# DDR3.net
KiCad netlist of a schematic drawn in Altium Designer
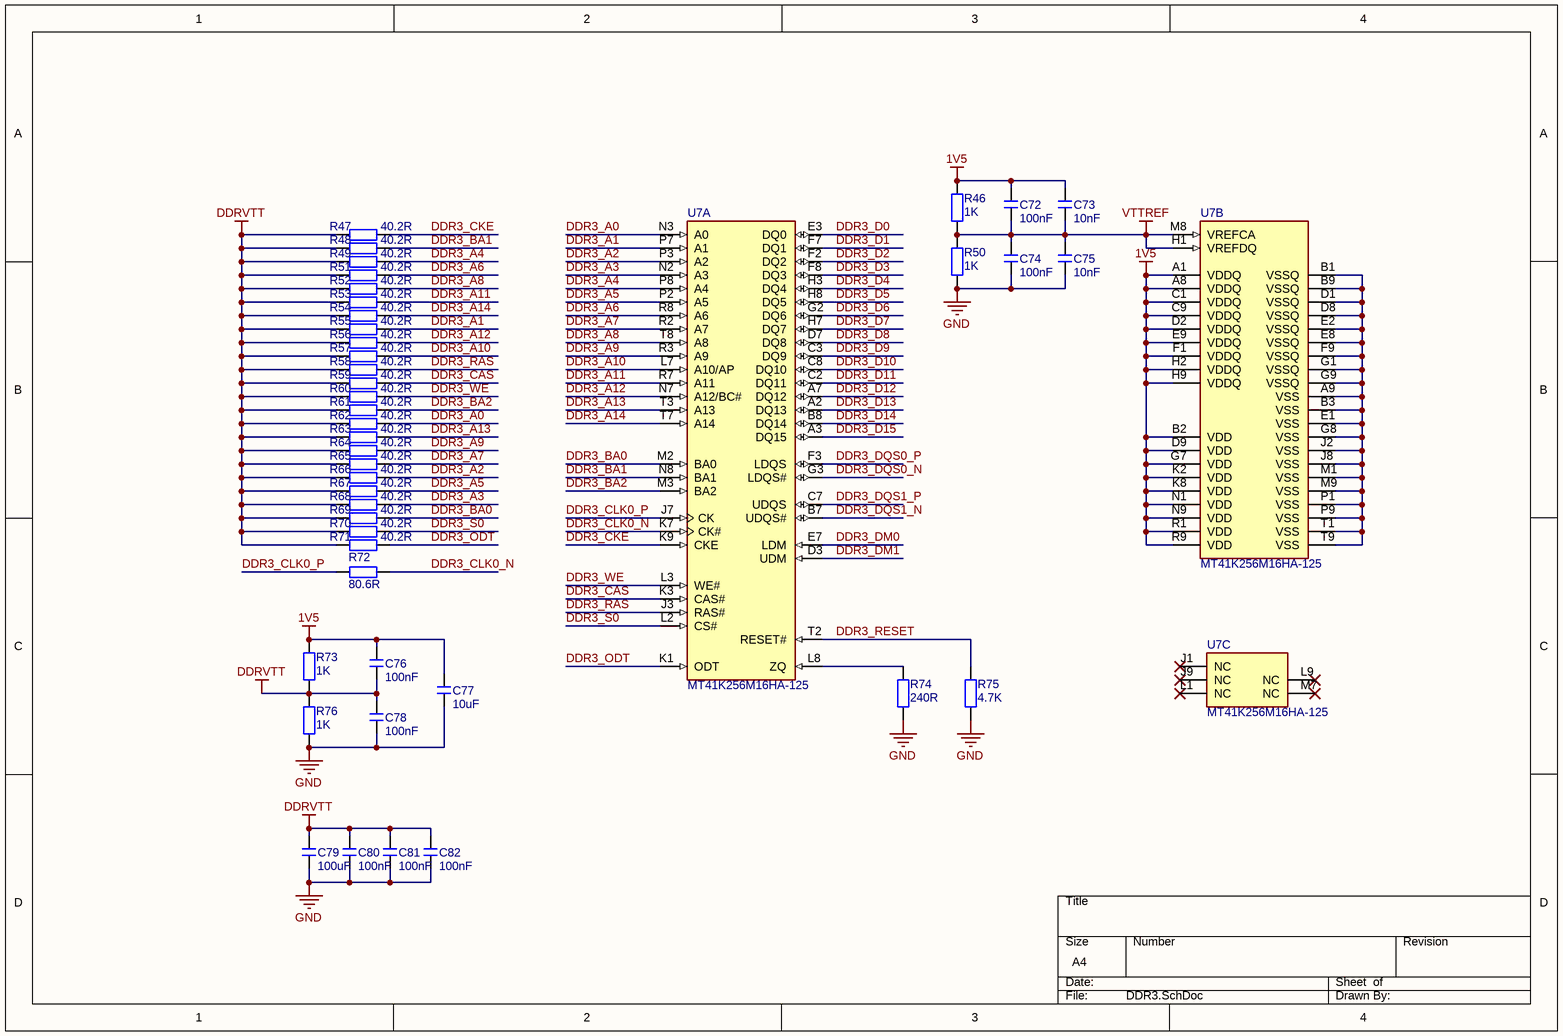
[diagram p0: DDR3.SchDoc]

(export (version "E")
  (design (tool "Eeschema 10.0.6"))
  (components
    (comp (ref "C72")
      (value "100nF")
      (footprint "C 0402_L")
      (description "无极性贴片电容")
      (fields (field (name "版权归属") "源创客"))
      (libsource (lib "3.1   - 电阻-电容-电感") (part "C"))
    )
    (comp (ref "C73")
      (value "10nF")
      (footprint "C 0402_L")
      (description "无极性贴片电容")
      (fields (field (name "版权归属") "源创客"))
      (libsource (lib "3.1   - 电阻-电容-电感") (part "C"))
    )
    (comp (ref "C74")
      (value "100nF")
      (footprint "C 0402_L")
      (description "无极性贴片电容")
      (fields (field (name "版权归属") "源创客"))
      (libsource (lib "3.1   - 电阻-电容-电感") (part "C"))
    )
    (comp (ref "C75")
      (value "10nF")
      (footprint "C 0402_L")
      (description "无极性贴片电容")
      (fields (field (name "版权归属") "源创客"))
      (libsource (lib "3.1   - 电阻-电容-电感") (part "C"))
    )
    (comp (ref "C76")
      (value "100nF")
      (footprint "C 0402_L")
      (description "无极性贴片电容")
      (fields (field (name "版权归属") "源创客"))
      (libsource (lib "3.1   - 电阻-电容-电感") (part "C"))
    )
    (comp (ref "C77")
      (value "10uF")
      (footprint "C 0603_L")
      (description "无极性贴片电容")
      (fields (field (name "版权归属") "源创客"))
      (libsource (lib "3.1   - 电阻-电容-电感") (part "C"))
    )
    (comp (ref "C78")
      (value "100nF")
      (footprint "C 0402_L")
      (description "无极性贴片电容")
      (fields (field (name "版权归属") "源创客"))
      (libsource (lib "3.1   - 电阻-电容-电感") (part "C"))
    )
    (comp (ref "C79")
      (value "100uF")
      (footprint "C 0805_L")
      (description "无极性贴片电容")
      (fields (field (name "版权归属") "源创客"))
      (libsource (lib "3.1   - 电阻-电容-电感") (part "C"))
    )
    (comp (ref "C80")
      (value "100nF")
      (footprint "C 0402_L")
      (description "无极性贴片电容")
      (fields (field (name "版权归属") "源创客"))
      (libsource (lib "3.1   - 电阻-电容-电感") (part "C"))
    )
    (comp (ref "C81")
      (value "100nF")
      (footprint "C 0402_L")
      (description "无极性贴片电容")
      (fields (field (name "版权归属") "源创客"))
      (libsource (lib "3.1   - 电阻-电容-电感") (part "C"))
    )
    (comp (ref "C82")
      (value "100nF")
      (footprint "C 0402_L")
      (description "无极性贴片电容")
      (fields (field (name "版权归属") "源创客"))
      (libsource (lib "3.1   - 电阻-电容-电感") (part "C"))
    )
    (comp (ref "R46")
      (value "1K")
      (footprint "R 0402_L")
      (description "贴片电阻")
      (fields (field (name "版权归属") "源创客"))
      (libsource (lib "3.1   - 电阻-电容-电感") (part "R"))
    )
    (comp (ref "R47")
      (value "40.2R")
      (footprint "R 0805_L")
      (description "贴片电阻")
      (fields (field (name "版权归属") "源创客"))
      (libsource (lib "3.1   - 电阻-电容-电感") (part "R"))
    )
    (comp (ref "R48")
      (value "40.2R")
      (footprint "R 0805_L")
      (description "贴片电阻")
      (fields (field (name "版权归属") "源创客"))
      (libsource (lib "3.1   - 电阻-电容-电感") (part "R"))
    )
    (comp (ref "R49")
      (value "40.2R")
      (footprint "R 0805_L")
      (description "贴片电阻")
      (fields (field (name "版权归属") "源创客"))
      (libsource (lib "3.1   - 电阻-电容-电感") (part "R"))
    )
    (comp (ref "R50")
      (value "1K")
      (footprint "R 0402_L")
      (description "贴片电阻")
      (fields (field (name "版权归属") "源创客"))
      (libsource (lib "3.1   - 电阻-电容-电感") (part "R"))
    )
    (comp (ref "R51")
      (value "40.2R")
      (footprint "R 0805_L")
      (description "贴片电阻")
      (fields (field (name "版权归属") "源创客"))
      (libsource (lib "3.1   - 电阻-电容-电感") (part "R"))
    )
    (comp (ref "R52")
      (value "40.2R")
      (footprint "R 0805_L")
      (description "贴片电阻")
      (fields (field (name "版权归属") "源创客"))
      (libsource (lib "3.1   - 电阻-电容-电感") (part "R"))
    )
    (comp (ref "R53")
      (value "40.2R")
      (footprint "R 0805_L")
      (description "贴片电阻")
      (fields (field (name "版权归属") "源创客"))
      (libsource (lib "3.1   - 电阻-电容-电感") (part "R"))
    )
    (comp (ref "R54")
      (value "40.2R")
      (footprint "R 0805_L")
      (description "贴片电阻")
      (fields (field (name "版权归属") "源创客"))
      (libsource (lib "3.1   - 电阻-电容-电感") (part "R"))
    )
    (comp (ref "R55")
      (value "40.2R")
      (footprint "R 0805_L")
      (description "贴片电阻")
      (fields (field (name "版权归属") "源创客"))
      (libsource (lib "3.1   - 电阻-电容-电感") (part "R"))
    )
    (comp (ref "R56")
      (value "40.2R")
      (footprint "R 0805_L")
      (description "贴片电阻")
      (fields (field (name "版权归属") "源创客"))
      (libsource (lib "3.1   - 电阻-电容-电感") (part "R"))
    )
    (comp (ref "R57")
      (value "40.2R")
      (footprint "R 0805_L")
      (description "贴片电阻")
      (fields (field (name "版权归属") "源创客"))
      (libsource (lib "3.1   - 电阻-电容-电感") (part "R"))
    )
    (comp (ref "R58")
      (value "40.2R")
      (footprint "R 0805_L")
      (description "贴片电阻")
      (fields (field (name "版权归属") "源创客"))
      (libsource (lib "3.1   - 电阻-电容-电感") (part "R"))
    )
    (comp (ref "R59")
      (value "40.2R")
      (footprint "R 0805_L")
      (description "贴片电阻")
      (fields (field (name "版权归属") "源创客"))
      (libsource (lib "3.1   - 电阻-电容-电感") (part "R"))
    )
    (comp (ref "R60")
      (value "40.2R")
      (footprint "R 0805_L")
      (description "贴片电阻")
      (fields (field (name "版权归属") "源创客"))
      (libsource (lib "3.1   - 电阻-电容-电感") (part "R"))
    )
    (comp (ref "R61")
      (value "40.2R")
      (footprint "R 0805_L")
      (description "贴片电阻")
      (fields (field (name "版权归属") "源创客"))
      (libsource (lib "3.1   - 电阻-电容-电感") (part "R"))
    )
    (comp (ref "R62")
      (value "40.2R")
      (footprint "R 0805_L")
      (description "贴片电阻")
      (fields (field (name "版权归属") "源创客"))
      (libsource (lib "3.1   - 电阻-电容-电感") (part "R"))
    )
    (comp (ref "R63")
      (value "40.2R")
      (footprint "R 0805_L")
      (description "贴片电阻")
      (fields (field (name "版权归属") "源创客"))
      (libsource (lib "3.1   - 电阻-电容-电感") (part "R"))
    )
    (comp (ref "R64")
      (value "40.2R")
      (footprint "R 0805_L")
      (description "贴片电阻")
      (fields (field (name "版权归属") "源创客"))
      (libsource (lib "3.1   - 电阻-电容-电感") (part "R"))
    )
    (comp (ref "R65")
      (value "40.2R")
      (footprint "R 0805_L")
      (description "贴片电阻")
      (fields (field (name "版权归属") "源创客"))
      (libsource (lib "3.1   - 电阻-电容-电感") (part "R"))
    )
    (comp (ref "R66")
      (value "40.2R")
      (footprint "R 0805_L")
      (description "贴片电阻")
      (fields (field (name "版权归属") "源创客"))
      (libsource (lib "3.1   - 电阻-电容-电感") (part "R"))
    )
    (comp (ref "R67")
      (value "40.2R")
      (footprint "R 0805_L")
      (description "贴片电阻")
      (fields (field (name "版权归属") "源创客"))
      (libsource (lib "3.1   - 电阻-电容-电感") (part "R"))
    )
    (comp (ref "R68")
      (value "40.2R")
      (footprint "R 0805_L")
      (description "贴片电阻")
      (fields (field (name "版权归属") "源创客"))
      (libsource (lib "3.1   - 电阻-电容-电感") (part "R"))
    )
    (comp (ref "R69")
      (value "40.2R")
      (footprint "R 0805_L")
      (description "贴片电阻")
      (fields (field (name "版权归属") "源创客"))
      (libsource (lib "3.1   - 电阻-电容-电感") (part "R"))
    )
    (comp (ref "R70")
      (value "40.2R")
      (footprint "R 0805_L")
      (description "贴片电阻")
      (fields (field (name "版权归属") "源创客"))
      (libsource (lib "3.1   - 电阻-电容-电感") (part "R"))
    )
    (comp (ref "R71")
      (value "40.2R")
      (footprint "R 0805_L")
      (description "贴片电阻")
      (fields (field (name "版权归属") "源创客"))
      (libsource (lib "3.1   - 电阻-电容-电感") (part "R"))
    )
    (comp (ref "R72")
      (value "80.6R")
      (footprint "R 0805_L")
      (description "贴片电阻")
      (fields (field (name "版权归属") "源创客"))
      (libsource (lib "3.1   - 电阻-电容-电感") (part "R"))
    )
    (comp (ref "R73")
      (value "1K")
      (footprint "R 0402_L")
      (description "贴片电阻")
      (fields (field (name "版权归属") "源创客"))
      (libsource (lib "3.1   - 电阻-电容-电感") (part "R"))
    )
    (comp (ref "R74")
      (value "240R")
      (footprint "R 0805_L")
      (description "贴片电阻")
      (fields (field (name "版权归属") "源创客"))
      (libsource (lib "3.1   - 电阻-电容-电感") (part "R"))
    )
    (comp (ref "R75")
      (value "4.7K")
      (footprint "R 0402_L")
      (description "贴片电阻")
      (fields (field (name "版权归属") "源创客"))
      (libsource (lib "3.1   - 电阻-电容-电感") (part "R"))
    )
    (comp (ref "R76")
      (value "1K")
      (footprint "R 0402_L")
      (description "贴片电阻")
      (fields (field (name "版权归属") "源创客"))
      (libsource (lib "3.1   - 电阻-电容-电感") (part "R"))
    )
    (comp (ref "U7")
      (value "MT41K256M16HA-125")
      (footprint "BGA96C80P9X16_800X1300X120")
      (description "DDR3-16位数据-14位地址")
      (libsource (lib "16.1 - DDR-LPDDR") (part "MT41K256M16HA-125"))
    )
  )
  (nets
    (net (code "1") (name "/DDR3_A0") (class "Default")
      (node (ref "R62") (pin "1") (pinfunction "1_1") (pintype "passive"))
      (node (ref "U7") (pin "N3") (pinfunction "A0_N3") (pintype "input"))
    )
    (net (code "2") (name "/DDR3_A1") (class "Default")
      (node (ref "R55") (pin "1") (pinfunction "1_1") (pintype "passive"))
      (node (ref "U7") (pin "P7") (pinfunction "A1_P7") (pintype "input"))
    )
    (net (code "3") (name "/DDR3_A2") (class "Default")
      (node (ref "R66") (pin "1") (pinfunction "1_1") (pintype "passive"))
      (node (ref "U7") (pin "P3") (pinfunction "A2_P3") (pintype "input"))
    )
    (net (code "4") (name "/DDR3_A3") (class "Default")
      (node (ref "R68") (pin "1") (pinfunction "1_1") (pintype "passive"))
      (node (ref "U7") (pin "N2") (pinfunction "A3_N2") (pintype "input"))
    )
    (net (code "5") (name "/DDR3_A4") (class "Default")
      (node (ref "R49") (pin "1") (pinfunction "1_1") (pintype "passive"))
      (node (ref "U7") (pin "P8") (pinfunction "A4_P8") (pintype "input"))
    )
    (net (code "6") (name "/DDR3_A5") (class "Default")
      (node (ref "R67") (pin "1") (pinfunction "1_1") (pintype "passive"))
      (node (ref "U7") (pin "P2") (pinfunction "A5_P2") (pintype "input"))
    )
    (net (code "7") (name "/DDR3_A6") (class "Default")
      (node (ref "R51") (pin "1") (pinfunction "1_1") (pintype "passive"))
      (node (ref "U7") (pin "R8") (pinfunction "A6_R8") (pintype "input"))
    )
    (net (code "8") (name "/DDR3_A7") (class "Default")
      (node (ref "R65") (pin "1") (pinfunction "1_1") (pintype "passive"))
      (node (ref "U7") (pin "R2") (pinfunction "A7_R2") (pintype "input"))
    )
    (net (code "9") (name "/DDR3_A8") (class "Default")
      (node (ref "R52") (pin "1") (pinfunction "1_1") (pintype "passive"))
      (node (ref "U7") (pin "T8") (pinfunction "A8_T8") (pintype "input"))
    )
    (net (code "10") (name "/DDR3_A9") (class "Default")
      (node (ref "R64") (pin "1") (pinfunction "1_1") (pintype "passive"))
      (node (ref "U7") (pin "R3") (pinfunction "A9_R3") (pintype "input"))
    )
    (net (code "11") (name "/DDR3_A10") (class "Default")
      (node (ref "R57") (pin "1") (pinfunction "1_1") (pintype "passive"))
      (node (ref "U7") (pin "L7") (pinfunction "A10/AP_L7") (pintype "input"))
    )
    (net (code "12") (name "/DDR3_A11") (class "Default")
      (node (ref "R53") (pin "1") (pinfunction "1_1") (pintype "passive"))
      (node (ref "U7") (pin "R7") (pinfunction "A11_R7") (pintype "input"))
    )
    (net (code "13") (name "/DDR3_A12") (class "Default")
      (node (ref "R56") (pin "1") (pinfunction "1_1") (pintype "passive"))
      (node (ref "U7") (pin "N7") (pinfunction "A12/BC#_N7") (pintype "input"))
    )
    (net (code "14") (name "/DDR3_A13") (class "Default")
      (node (ref "R63") (pin "1") (pinfunction "1_1") (pintype "passive"))
      (node (ref "U7") (pin "T3") (pinfunction "A13_T3") (pintype "input"))
    )
    (net (code "15") (name "/DDR3_A14") (class "Default")
      (node (ref "R54") (pin "1") (pinfunction "1_1") (pintype "passive"))
      (node (ref "U7") (pin "T7") (pinfunction "A14_T7") (pintype "input"))
    )
    (net (code "16") (name "/DDR3_BA0") (class "Default")
      (node (ref "R69") (pin "1") (pinfunction "1_1") (pintype "passive"))
      (node (ref "U7") (pin "M2") (pinfunction "BA0_M2") (pintype "input"))
    )
    (net (code "17") (name "/DDR3_BA1") (class "Default")
      (node (ref "R48") (pin "1") (pinfunction "1_1") (pintype "passive"))
      (node (ref "U7") (pin "N8") (pinfunction "BA1_N8") (pintype "input"))
    )
    (net (code "18") (name "/DDR3_BA2") (class "Default")
      (node (ref "R61") (pin "1") (pinfunction "1_1") (pintype "passive"))
      (node (ref "U7") (pin "M3") (pinfunction "BA2_M3") (pintype "input"))
    )
    (net (code "19") (name "/DDR3_CAS") (class "Default")
      (node (ref "R59") (pin "1") (pinfunction "1_1") (pintype "passive"))
      (node (ref "U7") (pin "K3") (pinfunction "CAS#_K3") (pintype "input"))
    )
    (net (code "20") (name "/DDR3_CKE") (class "Default")
      (node (ref "R47") (pin "1") (pinfunction "1_1") (pintype "passive"))
      (node (ref "U7") (pin "K9") (pinfunction "CKE_K9") (pintype "input"))
    )
    (net (code "21") (name "/DDR3_CLK0_N") (class "Default")
      (node (ref "R72") (pin "2") (pinfunction "2_2") (pintype "passive"))
      (node (ref "U7") (pin "K7") (pinfunction "CK#_K7") (pintype "input"))
    )
    (net (code "22") (name "/DDR3_CLK0_P") (class "Default")
      (node (ref "R72") (pin "1") (pinfunction "1_1") (pintype "passive"))
      (node (ref "U7") (pin "J7") (pinfunction "CK_J7") (pintype "input"))
    )
    (net (code "23") (name "/DDR3_D0") (class "Default")
      (node (ref "U7") (pin "E3") (pinfunction "DQ0_E3") (pintype "bidirectional"))
    )
    (net (code "24") (name "/DDR3_D1") (class "Default")
      (node (ref "U7") (pin "F7") (pinfunction "DQ1_F7") (pintype "bidirectional"))
    )
    (net (code "25") (name "/DDR3_D2") (class "Default")
      (node (ref "U7") (pin "F2") (pinfunction "DQ2_F2") (pintype "bidirectional"))
    )
    (net (code "26") (name "/DDR3_D3") (class "Default")
      (node (ref "U7") (pin "F8") (pinfunction "DQ3_F8") (pintype "bidirectional"))
    )
    (net (code "27") (name "/DDR3_D4") (class "Default")
      (node (ref "U7") (pin "H3") (pinfunction "DQ4_H3") (pintype "bidirectional"))
    )
    (net (code "28") (name "/DDR3_D5") (class "Default")
      (node (ref "U7") (pin "H8") (pinfunction "DQ5_H8") (pintype "bidirectional"))
    )
    (net (code "29") (name "/DDR3_D6") (class "Default")
      (node (ref "U7") (pin "G2") (pinfunction "DQ6_G2") (pintype "bidirectional"))
    )
    (net (code "30") (name "/DDR3_D7") (class "Default")
      (node (ref "U7") (pin "H7") (pinfunction "DQ7_H7") (pintype "bidirectional"))
    )
    (net (code "31") (name "/DDR3_D8") (class "Default")
      (node (ref "U7") (pin "D7") (pinfunction "DQ8_D7") (pintype "bidirectional"))
    )
    (net (code "32") (name "/DDR3_D9") (class "Default")
      (node (ref "U7") (pin "C3") (pinfunction "DQ9_C3") (pintype "bidirectional"))
    )
    (net (code "33") (name "/DDR3_D10") (class "Default")
      (node (ref "U7") (pin "C8") (pinfunction "DQ10_C8") (pintype "bidirectional"))
    )
    (net (code "34") (name "/DDR3_D11") (class "Default")
      (node (ref "U7") (pin "C2") (pinfunction "DQ11_C2") (pintype "bidirectional"))
    )
    (net (code "35") (name "/DDR3_D12") (class "Default")
      (node (ref "U7") (pin "A7") (pinfunction "DQ12_A7") (pintype "bidirectional"))
    )
    (net (code "36") (name "/DDR3_D13") (class "Default")
      (node (ref "U7") (pin "A2") (pinfunction "DQ13_A2") (pintype "bidirectional"))
    )
    (net (code "37") (name "/DDR3_D14") (class "Default")
      (node (ref "U7") (pin "B8") (pinfunction "DQ14_B8") (pintype "bidirectional"))
    )
    (net (code "38") (name "/DDR3_D15") (class "Default")
      (node (ref "U7") (pin "A3") (pinfunction "DQ15_A3") (pintype "bidirectional"))
    )
    (net (code "39") (name "/DDR3_DM0") (class "Default")
      (node (ref "U7") (pin "E7") (pinfunction "LDM_E7") (pintype "input"))
    )
    (net (code "40") (name "/DDR3_DM1") (class "Default")
      (node (ref "U7") (pin "D3") (pinfunction "UDM_D3") (pintype "input"))
    )
    (net (code "41") (name "/DDR3_DQS0_N") (class "Default")
      (node (ref "U7") (pin "G3") (pinfunction "LDQS#_G3") (pintype "bidirectional"))
    )
    (net (code "42") (name "/DDR3_DQS0_P") (class "Default")
      (node (ref "U7") (pin "F3") (pinfunction "LDQS_F3") (pintype "bidirectional"))
    )
    (net (code "43") (name "/DDR3_DQS1_N") (class "Default")
      (node (ref "U7") (pin "B7") (pinfunction "UDQS#_B7") (pintype "bidirectional"))
    )
    (net (code "44") (name "/DDR3_DQS1_P") (class "Default")
      (node (ref "U7") (pin "C7") (pinfunction "UDQS_C7") (pintype "bidirectional"))
    )
    (net (code "45") (name "/DDR3_ODT") (class "Default")
      (node (ref "R71") (pin "1") (pinfunction "1_1") (pintype "passive"))
      (node (ref "U7") (pin "K1") (pinfunction "ODT_K1") (pintype "input"))
    )
    (net (code "46") (name "/DDR3_RAS") (class "Default")
      (node (ref "R58") (pin "1") (pinfunction "1_1") (pintype "passive"))
      (node (ref "U7") (pin "J3") (pinfunction "RAS#_J3") (pintype "input"))
    )
    (net (code "47") (name "/DDR3_RESET") (class "Default")
      (node (ref "R75") (pin "1") (pinfunction "1_1") (pintype "passive"))
      (node (ref "U7") (pin "T2") (pinfunction "RESET#_T2") (pintype "input"))
    )
    (net (code "48") (name "/DDR3_S0") (class "Default")
      (node (ref "R70") (pin "1") (pinfunction "1_1") (pintype "passive"))
      (node (ref "U7") (pin "L2") (pinfunction "CS#_L2") (pintype "input"))
    )
    (net (code "49") (name "/DDR3_WE") (class "Default")
      (node (ref "R60") (pin "1") (pinfunction "1_1") (pintype "passive"))
      (node (ref "U7") (pin "L3") (pinfunction "WE#_L3") (pintype "input"))
    )
    (net (code "50") (name "1V5") (class "Default")
      (node (ref "C72") (pin "2") (pinfunction "2_2") (pintype "passive"))
      (node (ref "C73") (pin "2") (pinfunction "2_2") (pintype "passive"))
      (node (ref "C76") (pin "2") (pinfunction "2_2") (pintype "passive"))
      (node (ref "C77") (pin "2") (pinfunction "2_2") (pintype "passive"))
      (node (ref "R46") (pin "2") (pinfunction "2_2") (pintype "passive"))
      (node (ref "R73") (pin "1") (pinfunction "1_1") (pintype "passive"))
      (node (ref "U7") (pin "A1") (pinfunction "VDDQ_A1") (pintype "power_in"))
      (node (ref "U7") (pin "A8") (pinfunction "VDDQ_A8") (pintype "power_in"))
      (node (ref "U7") (pin "B2") (pinfunction "VDD_B2") (pintype "power_in"))
      (node (ref "U7") (pin "C1") (pinfunction "VDDQ_C1") (pintype "power_in"))
      (node (ref "U7") (pin "C9") (pinfunction "VDDQ_C9") (pintype "power_in"))
      (node (ref "U7") (pin "D2") (pinfunction "VDDQ_D2") (pintype "power_in"))
      (node (ref "U7") (pin "D9") (pinfunction "VDD_D9") (pintype "power_in"))
      (node (ref "U7") (pin "E9") (pinfunction "VDDQ_E9") (pintype "power_in"))
      (node (ref "U7") (pin "F1") (pinfunction "VDDQ_F1") (pintype "power_in"))
      (node (ref "U7") (pin "G7") (pinfunction "VDD_G7") (pintype "power_in"))
      (node (ref "U7") (pin "H2") (pinfunction "VDDQ_H2") (pintype "power_in"))
      (node (ref "U7") (pin "H9") (pinfunction "VDDQ_H9") (pintype "power_in"))
      (node (ref "U7") (pin "K2") (pinfunction "VDD_K2") (pintype "power_in"))
      (node (ref "U7") (pin "K8") (pinfunction "VDD_K8") (pintype "power_in"))
      (node (ref "U7") (pin "N1") (pinfunction "VDD_N1") (pintype "power_in"))
      (node (ref "U7") (pin "N9") (pinfunction "VDD_N9") (pintype "power_in"))
      (node (ref "U7") (pin "R1") (pinfunction "VDD_R1") (pintype "power_in"))
      (node (ref "U7") (pin "R9") (pinfunction "VDD_R9") (pintype "power_in"))
    )
    (net (code "51") (name "DDRVTT") (class "Default")
      (node (ref "C76") (pin "1") (pinfunction "1_1") (pintype "passive"))
      (node (ref "C78") (pin "2") (pinfunction "2_2") (pintype "passive"))
      (node (ref "C79") (pin "2") (pinfunction "2_2") (pintype "passive"))
      (node (ref "C80") (pin "2") (pinfunction "2_2") (pintype "passive"))
      (node (ref "C81") (pin "2") (pinfunction "2_2") (pintype "passive"))
      (node (ref "C82") (pin "2") (pinfunction "2_2") (pintype "passive"))
      (node (ref "R47") (pin "2") (pinfunction "2_2") (pintype "passive"))
      (node (ref "R48") (pin "2") (pinfunction "2_2") (pintype "passive"))
      (node (ref "R49") (pin "2") (pinfunction "2_2") (pintype "passive"))
      (node (ref "R51") (pin "2") (pinfunction "2_2") (pintype "passive"))
      (node (ref "R52") (pin "2") (pinfunction "2_2") (pintype "passive"))
      (node (ref "R53") (pin "2") (pinfunction "2_2") (pintype "passive"))
      (node (ref "R54") (pin "2") (pinfunction "2_2") (pintype "passive"))
      (node (ref "R55") (pin "2") (pinfunction "2_2") (pintype "passive"))
      (node (ref "R56") (pin "2") (pinfunction "2_2") (pintype "passive"))
      (node (ref "R57") (pin "2") (pinfunction "2_2") (pintype "passive"))
      (node (ref "R58") (pin "2") (pinfunction "2_2") (pintype "passive"))
      (node (ref "R59") (pin "2") (pinfunction "2_2") (pintype "passive"))
      (node (ref "R60") (pin "2") (pinfunction "2_2") (pintype "passive"))
      (node (ref "R61") (pin "2") (pinfunction "2_2") (pintype "passive"))
      (node (ref "R62") (pin "2") (pinfunction "2_2") (pintype "passive"))
      (node (ref "R63") (pin "2") (pinfunction "2_2") (pintype "passive"))
      (node (ref "R64") (pin "2") (pinfunction "2_2") (pintype "passive"))
      (node (ref "R65") (pin "2") (pinfunction "2_2") (pintype "passive"))
      (node (ref "R66") (pin "2") (pinfunction "2_2") (pintype "passive"))
      (node (ref "R67") (pin "2") (pinfunction "2_2") (pintype "passive"))
      (node (ref "R68") (pin "2") (pinfunction "2_2") (pintype "passive"))
      (node (ref "R69") (pin "2") (pinfunction "2_2") (pintype "passive"))
      (node (ref "R70") (pin "2") (pinfunction "2_2") (pintype "passive"))
      (node (ref "R71") (pin "2") (pinfunction "2_2") (pintype "passive"))
      (node (ref "R73") (pin "2") (pinfunction "2_2") (pintype "passive"))
      (node (ref "R76") (pin "1") (pinfunction "1_1") (pintype "passive"))
    )
    (net (code "52") (name "GND") (class "Default")
      (node (ref "C74") (pin "1") (pinfunction "1_1") (pintype "passive"))
      (node (ref "C75") (pin "1") (pinfunction "1_1") (pintype "passive"))
      (node (ref "C77") (pin "1") (pinfunction "1_1") (pintype "passive"))
      (node (ref "C78") (pin "1") (pinfunction "1_1") (pintype "passive"))
      (node (ref "C79") (pin "1") (pinfunction "1_1") (pintype "passive"))
      (node (ref "C80") (pin "1") (pinfunction "1_1") (pintype "passive"))
      (node (ref "C81") (pin "1") (pinfunction "1_1") (pintype "passive"))
      (node (ref "C82") (pin "1") (pinfunction "1_1") (pintype "passive"))
      (node (ref "R50") (pin "1") (pinfunction "1_1") (pintype "passive"))
      (node (ref "R74") (pin "2") (pinfunction "2_2") (pintype "passive"))
      (node (ref "R75") (pin "2") (pinfunction "2_2") (pintype "passive"))
      (node (ref "R76") (pin "2") (pinfunction "2_2") (pintype "passive"))
    )
    (net (code "53") (name "Net-(U7A-ZQ)") (class "Default")
      (node (ref "R74") (pin "1") (pinfunction "1_1") (pintype "passive"))
      (node (ref "U7") (pin "L8") (pinfunction "ZQ_L8") (pintype "input"))
    )
    (net (code "54") (name "Net-(U7B-VSS-PadA9)") (class "Default")
      (node (ref "U7") (pin "A9") (pinfunction "VSS_A9") (pintype "power_in"))
      (node (ref "U7") (pin "B1") (pinfunction "VSSQ_B1") (pintype "power_in"))
      (node (ref "U7") (pin "B3") (pinfunction "VSS_B3") (pintype "power_in"))
      (node (ref "U7") (pin "B9") (pinfunction "VSSQ_B9") (pintype "power_in"))
      (node (ref "U7") (pin "D1") (pinfunction "VSSQ_D1") (pintype "power_in"))
      (node (ref "U7") (pin "D8") (pinfunction "VSSQ_D8") (pintype "power_in"))
      (node (ref "U7") (pin "E1") (pinfunction "VSS_E1") (pintype "power_in"))
      (node (ref "U7") (pin "E2") (pinfunction "VSSQ_E2") (pintype "power_in"))
      (node (ref "U7") (pin "E8") (pinfunction "VSSQ_E8") (pintype "power_in"))
      (node (ref "U7") (pin "F9") (pinfunction "VSSQ_F9") (pintype "power_in"))
      (node (ref "U7") (pin "G1") (pinfunction "VSSQ_G1") (pintype "power_in"))
      (node (ref "U7") (pin "G8") (pinfunction "VSS_G8") (pintype "power_in"))
      (node (ref "U7") (pin "G9") (pinfunction "VSSQ_G9") (pintype "power_in"))
      (node (ref "U7") (pin "J2") (pinfunction "VSS_J2") (pintype "power_in"))
      (node (ref "U7") (pin "J8") (pinfunction "VSS_J8") (pintype "power_in"))
      (node (ref "U7") (pin "M1") (pinfunction "VSS_M1") (pintype "power_in"))
      (node (ref "U7") (pin "M9") (pinfunction "VSS_M9") (pintype "power_in"))
      (node (ref "U7") (pin "P1") (pinfunction "VSS_P1") (pintype "power_in"))
      (node (ref "U7") (pin "P9") (pinfunction "VSS_P9") (pintype "power_in"))
      (node (ref "U7") (pin "T1") (pinfunction "VSS_T1") (pintype "power_in"))
      (node (ref "U7") (pin "T9") (pinfunction "VSS_T9") (pintype "power_in"))
    )
    (net (code "55") (name "VTTREF") (class "Default")
      (node (ref "C72") (pin "1") (pinfunction "1_1") (pintype "passive"))
      (node (ref "C73") (pin "1") (pinfunction "1_1") (pintype "passive"))
      (node (ref "C74") (pin "2") (pinfunction "2_2") (pintype "passive"))
      (node (ref "C75") (pin "2") (pinfunction "2_2") (pintype "passive"))
      (node (ref "R46") (pin "1") (pinfunction "1_1") (pintype "passive"))
      (node (ref "R50") (pin "2") (pinfunction "2_2") (pintype "passive"))
      (node (ref "U7") (pin "H1") (pinfunction "VREFDQ_H1") (pintype "input"))
      (node (ref "U7") (pin "M8") (pinfunction "VREFCA_M8") (pintype "input"))
    )
    (net (code "56") (name "unconnected-(U7C-NC-PadJ1)") (class "Default")
      (node (ref "U7") (pin "J1") (pinfunction "NC_J1") (pintype "passive+no_connect"))
    )
    (net (code "57") (name "unconnected-(U7C-NC-PadJ9)") (class "Default")
      (node (ref "U7") (pin "J9") (pinfunction "NC_J9") (pintype "passive+no_connect"))
    )
    (net (code "58") (name "unconnected-(U7C-NC-PadL1)") (class "Default")
      (node (ref "U7") (pin "L1") (pinfunction "NC_L1") (pintype "passive+no_connect"))
    )
    (net (code "59") (name "unconnected-(U7C-NC-PadL9)") (class "Default")
      (node (ref "U7") (pin "L9") (pinfunction "NC_L9") (pintype "passive+no_connect"))
    )
    (net (code "60") (name "unconnected-(U7C-NC-PadM7)") (class "Default")
      (node (ref "U7") (pin "M7") (pinfunction "NC_M7") (pintype "passive+no_connect"))
    )
  )
)
